# USB_MINI_B.net
KiCad netlist of a schematic drawn in Altium Designer
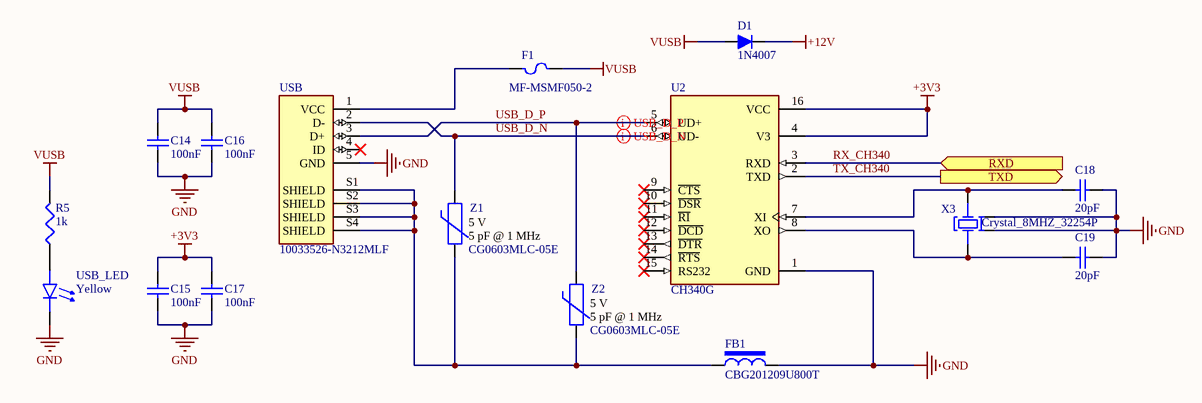
[diagram p0: USB_MINI_B.SchDoc]

(export (version "E")
  (design (tool "Eeschema 10.0.6"))
  (components
    (comp (ref "C14")
      (value "100nF")
      (footprint "CAPC0805(2012)145_L")
      (description "Chip Capacitor, 100nF +/-40%, 16V, 0805, Thickness 1.45 mm")
      (fields (field (name "TOLERANCE") "5%"))
      (libsource (lib "Ho Chi Minh City University of Technology") (part "CAP-NP-2"))
    )
    (comp (ref "C15")
      (value "100nF")
      (footprint "CAPC0805(2012)145_L")
      (description "Chip Capacitor, 100nF +/-40%, 16V, 0805, Thickness 1.45 mm")
      (fields (field (name "TOLERANCE") "5%"))
      (libsource (lib "Ho Chi Minh City University of Technology") (part "CAP-NP-2"))
    )
    (comp (ref "C16")
      (value "100nF")
      (footprint "CAPC0805(2012)145_L")
      (description "Chip Capacitor, 100nF +/-40%, 16V, 0805, Thickness 1.45 mm")
      (fields (field (name "TOLERANCE") "5%"))
      (libsource (lib "Ho Chi Minh City University of Technology") (part "CAP-NP-2"))
    )
    (comp (ref "C17")
      (value "100nF")
      (footprint "CAPC0805(2012)145_L")
      (description "Chip Capacitor, 100nF +/-40%, 16V, 0805, Thickness 1.45 mm")
      (fields (field (name "TOLERANCE") "5%"))
      (libsource (lib "Ho Chi Minh City University of Technology") (part "CAP-NP-2"))
    )
    (comp (ref "C18")
      (value "20pF")
      (footprint "CAPC0805(2012)145_L")
      (description "Chip Capacitor, 22µF +/-40%, 16V, 0805, Thickness 1.45 mm")
      (fields (field (name "TOLERANCE") "5%") (field (name "Comment") "22uF"))
      (libsource (lib "Ho Chi Minh City University of Technology") (part "CAP-NP-2"))
    )
    (comp (ref "C19")
      (value "20pF")
      (footprint "CAPC0805(2012)145_L")
      (description "Chip Capacitor, 22µF +/-40%, 16V, 0805, Thickness 1.45 mm")
      (fields (field (name "TOLERANCE") "5%") (field (name "Comment") "22uF"))
      (libsource (lib "Ho Chi Minh City University of Technology") (part "CAP-NP-2"))
    )
    (comp (ref "D1")
      (value "1N4007")
      (footprint "1N4007")
      (fields (field (name "JLCPCB PART #") "C95872"))
      (libsource (lib "Ho Chi Minh City University of Technology") (part "diode"))
    )
    (comp (ref "F1")
      (value "MF-MSMF050-2")
      (footprint "1812 (4532 Metric), Concave")
      (description "https://www.thegioiic.com/mf-msmf050-2-cau-chi-tu-phuc-hoi-1812-15v-0-5a")
      (fields
        (field (name "PART NUMBER") "MF-MSMF050-2")
        (field (name "JLCPCB PART #") "C17313")
        (field (name "SOURCE") "[CO2037] Power Consumption Calculator Arduino Board.SCHLIB")
      )
      (libsource (lib "TRẦN HẢI THẢO QUẢNG") (part "CMP-005-00015-2"))
    )
    (comp (ref "FB1")
      (value "CBG201209U800T")
      (footprint "0805 (2012 Metric)")
      (fields (field (name "JLCPCB PART #") "C139149") (field (name "DESIGN ITEM ID") "CBG201209U800T"))
      (libsource (lib "Ho Chi Minh City University of Technology") (part "Ferrite Bead"))
    )
    (comp (ref "R5")
      (value "1k")
      (footprint "0805 (2012 Metric)")
      (description "Oreki")
      (libsource (lib "Ho Chi Minh City University of Technology") (part "RES-2"))
    )
    (comp (ref "U2")
      (value "CH340G")
      (footprint "SOIC127P600X180-16N")
      (description "USB Interface Integrated Circuit")
      (fields (field (name "MF") "WCH") (field (name "MP") "Ch340G"))
      (libsource (lib "Ho Chi Minh City University of Technology") (part "CH340G"))
    )
    (comp (ref "USB")
      (value "10033526-N3212MLF")
      (footprint "AMPHENOL_10033526-N3212MLF")
      (description "USB - mini B Receptacle Connector 5 Position Surface Mount, Right Angle")
      (fields (field (name "MF") "Amphenol ICC") (field (name "JLCPCB PART #") "C2681563"))
      (libsource (lib "Ho Chi Minh City University of Technology") (part "10033526-N3212MLF"))
    )
    (comp (ref "USB_LED")
      (value "Yellow")
      (footprint "0805 (2012 Metric) Yellow")
      (description "Oreki")
      (fields (field (name "JLCPCB PART #") "C2296"))
      (libsource (lib "Ho Chi Minh City University of Technology") (part "Symbol"))
    )
    (comp (ref "X3")
      (value "Crystal_8MHZ_32254P")
      (footprint "4-SMD, No Lead (3.2mm x 2.5mm)")
      (description "SMD3225-4P")
      (fields (field (name "JLCPCB PART #") "C2682774"))
      (libsource (lib "Ho Chi Minh City University of Technology") (part "Crystal"))
    )
    (comp (ref "Z1")
      (value "CG0603MLC-05E")
      (footprint "0603 (1608 Metric)")
      (description "chua co link, xem tam: https://www.thegioiic.com/cg0603mlc-05e")
      (fields
        (field (name "CAPACITANCE @ FREQUENCY") "5 pF @ 1 MHz")
        (field (name "MAXIMUM DC VOLTS") "5 V")
        (field (name "PART NUMBER") "CG0603MLC-05E")
        (field (name "JLCPCB PART #") "C840634")
        (field (name "SOURCE") "[CO2037] Power Consumption Calculator Arduino Board.SCHLIB")
      )
      (libsource (lib "TRẦN HẢI THẢO QUẢNG") (part "CMP-001-00088-1"))
    )
    (comp (ref "Z2")
      (value "CG0603MLC-05E")
      (footprint "0603 (1608 Metric)")
      (description "chua co link, xem tam: https://www.thegioiic.com/cg0603mlc-05e")
      (fields
        (field (name "CAPACITANCE @ FREQUENCY") "5 pF @ 1 MHz")
        (field (name "MAXIMUM DC VOLTS") "5 V")
        (field (name "PART NUMBER") "CG0603MLC-05E")
        (field (name "JLCPCB PART #") "C840634")
        (field (name "SOURCE") "[CO2037] Power Consumption Calculator Arduino Board.SCHLIB")
      )
      (libsource (lib "TRẦN HẢI THẢO QUẢNG") (part "CMP-001-00088-1"))
    )
  )
  (nets
    (net (code "1") (name "+3V3") (class "Default")
      (node (ref "C15") (pin "2") (pinfunction "2_2") (pintype "passive"))
      (node (ref "C17") (pin "2") (pinfunction "2_2") (pintype "passive"))
      (node (ref "U2") (pin "16") (pinfunction "VCC_16") (pintype "power_in"))
      (node (ref "U2") (pin "4") (pinfunction "V3_4") (pintype "power_in"))
    )
    (net (code "2") (name "+12V") (class "Default")
      (node (ref "D1") (pin "1") (pinfunction "1_1") (pintype "passive"))
    )
    (net (code "3") (name "/RX_CH340") (class "Default")
      (node (ref "U2") (pin "3") (pinfunction "RXD_3") (pintype "input"))
    )
    (net (code "4") (name "/TX_CH340") (class "Default")
      (node (ref "U2") (pin "2") (pinfunction "TXD_2") (pintype "output"))
    )
    (net (code "5") (name "/USB_D_N") (class "Default")
      (node (ref "U2") (pin "6") (pinfunction "UD-_6") (pintype "bidirectional"))
      (node (ref "USB") (pin "2") (pinfunction "D-_2") (pintype "bidirectional"))
      (node (ref "Z1") (pin "1") (pinfunction "1_1") (pintype "passive"))
    )
    (net (code "6") (name "/USB_D_P") (class "Default")
      (node (ref "U2") (pin "5") (pinfunction "UD+_5") (pintype "bidirectional"))
      (node (ref "USB") (pin "3") (pinfunction "D+_3") (pintype "bidirectional"))
      (node (ref "Z2") (pin "1") (pinfunction "1_1") (pintype "passive"))
    )
    (net (code "7") (name "GND") (class "Default")
      (node (ref "C14") (pin "1") (pinfunction "1_1") (pintype "passive"))
      (node (ref "C15") (pin "1") (pinfunction "1_1") (pintype "passive"))
      (node (ref "C16") (pin "1") (pinfunction "1_1") (pintype "passive"))
      (node (ref "C17") (pin "1") (pinfunction "1_1") (pintype "passive"))
      (node (ref "C18") (pin "2") (pinfunction "2_2") (pintype "passive"))
      (node (ref "C19") (pin "2") (pinfunction "2_2") (pintype "passive"))
      (node (ref "FB1") (pin "2") (pinfunction "2_2") (pintype "passive"))
      (node (ref "U2") (pin "1") (pinfunction "GND_1") (pintype "power_in"))
      (node (ref "USB") (pin "5") (pinfunction "GND_5") (pintype "power_in"))
      (node (ref "USB_LED") (pin "1") (pinfunction "K_1") (pintype "passive"))
      (node (ref "X3") (pin "2") (pinfunction "GND_2") (pintype "passive"))
      (node (ref "X3") (pin "4") (pinfunction "GND_4") (pintype "passive"))
    )
    (net (code "8") (name "Net-(FB1-Pad1)") (class "Default")
      (node (ref "FB1") (pin "1") (pinfunction "1_1") (pintype "passive"))
      (node (ref "USB") (pin "S1") (pinfunction "SHIELD_S1") (pintype "passive"))
      (node (ref "USB") (pin "S2") (pinfunction "SHIELD_S2") (pintype "passive"))
      (node (ref "USB") (pin "S3") (pinfunction "SHIELD_S3") (pintype "passive"))
      (node (ref "USB") (pin "S4") (pinfunction "SHIELD_S4") (pintype "passive"))
      (node (ref "Z1") (pin "2") (pinfunction "2_2") (pintype "passive"))
      (node (ref "Z2") (pin "2") (pinfunction "2_2") (pintype "passive"))
    )
    (net (code "9") (name "Net-(U2-XI)") (class "Default")
      (node (ref "C18") (pin "1") (pinfunction "1_1") (pintype "passive"))
      (node (ref "U2") (pin "7") (pinfunction "XI_7") (pintype "input"))
      (node (ref "X3") (pin "3") (pinfunction "3_3") (pintype "passive"))
    )
    (net (code "10") (name "Net-(U2-XO)") (class "Default")
      (node (ref "C19") (pin "1") (pinfunction "1_1") (pintype "passive"))
      (node (ref "U2") (pin "8") (pinfunction "XO_8") (pintype "output"))
      (node (ref "X3") (pin "1") (pinfunction "1_1") (pintype "passive"))
    )
    (net (code "11") (name "Net-(USB-VCC)") (class "Default")
      (node (ref "F1") (pin "1") (pinfunction "1_1") (pintype "passive"))
      (node (ref "USB") (pin "1") (pinfunction "VCC_1") (pintype "power_in"))
    )
    (net (code "12") (name "Net-(USB_LED-A)") (class "Default")
      (node (ref "R5") (pin "1") (pinfunction "1_1") (pintype "passive"))
      (node (ref "USB_LED") (pin "2") (pinfunction "A_2") (pintype "passive"))
    )
    (net (code "13") (name "VUSB") (class "Default")
      (node (ref "C14") (pin "2") (pinfunction "2_2") (pintype "passive"))
      (node (ref "C16") (pin "2") (pinfunction "2_2") (pintype "passive"))
      (node (ref "D1") (pin "2") (pinfunction "2_2") (pintype "passive"))
      (node (ref "F1") (pin "2") (pinfunction "2_2") (pintype "passive"))
      (node (ref "R5") (pin "2") (pinfunction "2_2") (pintype "passive"))
    )
    (net (code "14") (name "unconnected-(U2-RS232-Pad15)") (class "Default")
      (node (ref "U2") (pin "15") (pinfunction "RS232_15") (pintype "input+no_connect"))
    )
    (net (code "15") (name "unconnected-(U2-~{CTS}-Pad9)") (class "Default")
      (node (ref "U2") (pin "9") (pinfunction "~{CTS}_9") (pintype "input+no_connect"))
    )
    (net (code "16") (name "unconnected-(U2-~{DCD}-Pad12)") (class "Default")
      (node (ref "U2") (pin "12") (pinfunction "~{DCD}_12") (pintype "input+no_connect"))
    )
    (net (code "17") (name "unconnected-(U2-~{DSR}-Pad10)") (class "Default")
      (node (ref "U2") (pin "10") (pinfunction "~{DSR}_10") (pintype "input+no_connect"))
    )
    (net (code "18") (name "unconnected-(U2-~{DTR}-Pad13)") (class "Default")
      (node (ref "U2") (pin "13") (pinfunction "~{DTR}_13") (pintype "output+no_connect"))
    )
    (net (code "19") (name "unconnected-(U2-~{RI}-Pad11)") (class "Default")
      (node (ref "U2") (pin "11") (pinfunction "~{RI}_11") (pintype "input+no_connect"))
    )
    (net (code "20") (name "unconnected-(U2-~{RTS}-Pad14)") (class "Default")
      (node (ref "U2") (pin "14") (pinfunction "~{RTS}_14") (pintype "output+no_connect"))
    )
    (net (code "21") (name "unconnected-(USB-ID-Pad4)") (class "Default")
      (node (ref "USB") (pin "4") (pinfunction "ID_4") (pintype "bidirectional+no_connect"))
    )
  )
)
